# sensors.net
KiCad netlist of a schematic drawn in EAGLE
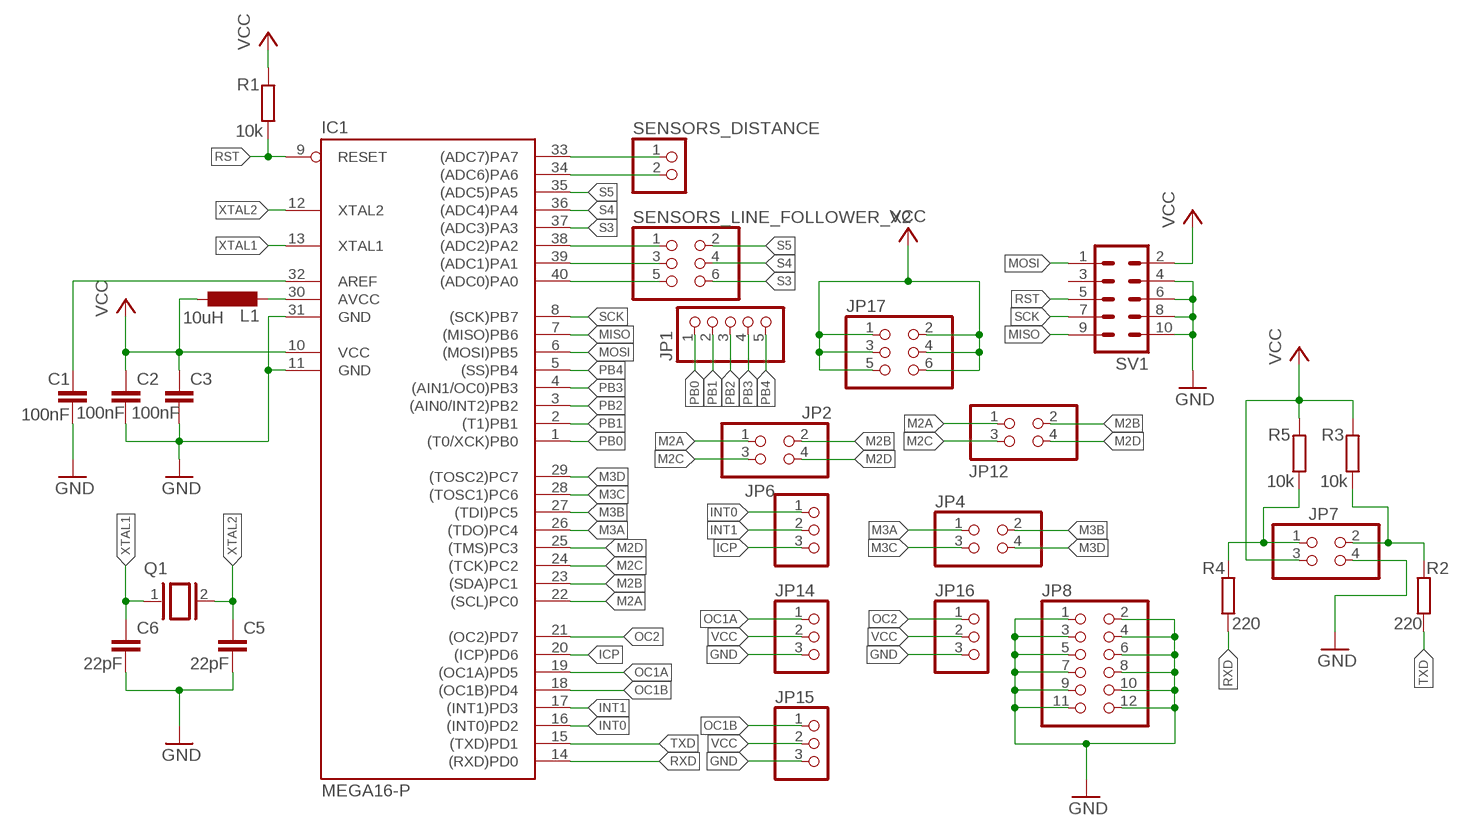
[diagram p0: schematic, sheet 1]

(export (version "E")
  (design (tool "Eeschema 10.0.6"))
  (components
    (comp (ref "C1")
      (value "100nF")
      (footprint "eagle-import:C0805")
      (libsource (lib "eagle-import") (part "C-EUC0805"))
    )
    (comp (ref "C2")
      (value "100nF")
      (footprint "eagle-import:C0805")
      (libsource (lib "eagle-import") (part "C-EUC0805"))
    )
    (comp (ref "C3")
      (value "100nF")
      (footprint "eagle-import:C0805")
      (libsource (lib "eagle-import") (part "C-EUC0805"))
    )
    (comp (ref "C5")
      (value "22pF")
      (footprint "eagle-import:C0805")
      (libsource (lib "eagle-import") (part "C-EUC0805"))
    )
    (comp (ref "C6")
      (value "22pF")
      (footprint "eagle-import:C0805")
      (libsource (lib "eagle-import") (part "C-EUC0805"))
    )
    (comp (ref "IC1")
      (value "MEGA16-P")
      (footprint "eagle-import:DIL40")
      (fields (field (name "MPN") "ATMEGA16-16PU"))
      (libsource (lib "eagle-import") (part "MEGA16-P"))
    )
    (comp (ref "JP1")
      (value "PINHD-1X5")
      (footprint "eagle-import:1X05")
      (libsource (lib "eagle-import") (part "PINHD-1X5"))
    )
    (comp (ref "JP2")
      (value "PINHD-2X2")
      (footprint "eagle-import:2X02")
      (libsource (lib "eagle-import") (part "PINHD-2X2"))
    )
    (comp (ref "JP4")
      (value "PINHD-2X2")
      (footprint "eagle-import:2X02")
      (libsource (lib "eagle-import") (part "PINHD-2X2"))
    )
    (comp (ref "JP6")
      (value "PINHD-1X3")
      (footprint "eagle-import:1X03")
      (libsource (lib "eagle-import") (part "PINHD-1X3"))
    )
    (comp (ref "JP7")
      (value "PINHD-2X2")
      (footprint "eagle-import:2X02")
      (libsource (lib "eagle-import") (part "PINHD-2X2"))
    )
    (comp (ref "JP8")
      (value "PINHD-2X6")
      (footprint "eagle-import:2X06")
      (libsource (lib "eagle-import") (part "PINHD-2X6"))
    )
    (comp (ref "JP12")
      (value "PINHD-2X2")
      (footprint "eagle-import:2X02")
      (libsource (lib "eagle-import") (part "PINHD-2X2"))
    )
    (comp (ref "JP14")
      (value "PINHD-1X3")
      (footprint "eagle-import:1X03")
      (libsource (lib "eagle-import") (part "PINHD-1X3"))
    )
    (comp (ref "JP15")
      (value "PINHD-1X3")
      (footprint "eagle-import:1X03")
      (libsource (lib "eagle-import") (part "PINHD-1X3"))
    )
    (comp (ref "JP16")
      (value "PINHD-1X3")
      (footprint "eagle-import:1X03")
      (libsource (lib "eagle-import") (part "PINHD-1X3"))
    )
    (comp (ref "JP17")
      (value "PINHD-2X3")
      (footprint "eagle-import:2X03")
      (libsource (lib "eagle-import") (part "PINHD-2X3"))
    )
    (comp (ref "L1")
      (value "10uH")
      (footprint "eagle-import:0207_7")
      (libsource (lib "eagle-import") (part "L-EU0207/7"))
    )
    (comp (ref "Q1")
      (value "XTAL/S")
      (footprint "eagle-import:QS")
      (libsource (lib "eagle-import") (part "XTAL/S"))
    )
    (comp (ref "R1")
      (value "10k")
      (footprint "eagle-import:R0805")
      (libsource (lib "eagle-import") (part "R-EU_R0805"))
    )
    (comp (ref "R2")
      (value "220")
      (footprint "eagle-import:R0805")
      (libsource (lib "eagle-import") (part "R-EU_R0805"))
    )
    (comp (ref "R3")
      (value "10k")
      (footprint "eagle-import:R0805")
      (libsource (lib "eagle-import") (part "R-EU_R0805"))
    )
    (comp (ref "R4")
      (value "220")
      (footprint "eagle-import:R0805")
      (libsource (lib "eagle-import") (part "R-EU_R0805"))
    )
    (comp (ref "R5")
      (value "10k")
      (footprint "eagle-import:R0805")
      (libsource (lib "eagle-import") (part "R-EU_R0805"))
    )
    (comp (ref "SENSORS_DISTANCE")
      (value "PINHD-1X2")
      (footprint "eagle-import:1X02")
      (libsource (lib "eagle-import") (part "PINHD-1X2"))
    )
    (comp (ref "SENSORS_LINE_FOLLOWER_X2")
      (value "PINHD-2X3")
      (footprint "eagle-import:2X03")
      (libsource (lib "eagle-import") (part "PINHD-2X3"))
    )
    (comp (ref "SV1")
      (value "ML10")
      (footprint "eagle-import:ML10")
      (libsource (lib "eagle-import") (part "ML10"))
    )
  )
  (nets
    (net (code "1") (name "GND") (class "Default")
      (node (ref "C1") (pin "2") (pinfunction "2_2") (pintype "passive"))
      (node (ref "C2") (pin "2") (pinfunction "2_2") (pintype "passive"))
      (node (ref "C3") (pin "2") (pinfunction "2_2") (pintype "passive"))
      (node (ref "C5") (pin "2") (pinfunction "2_2") (pintype "passive"))
      (node (ref "C6") (pin "2") (pinfunction "2_2") (pintype "passive"))
      (node (ref "IC1") (pin "11") (pinfunction "GND_11") (pintype "power_in"))
      (node (ref "IC1") (pin "31") (pinfunction "GND_31") (pintype "power_in"))
      (node (ref "JP14") (pin "3") (pinfunction "3_3") (pintype "passive"))
      (node (ref "JP15") (pin "3") (pinfunction "3_3") (pintype "passive"))
      (node (ref "JP16") (pin "3") (pinfunction "3_3") (pintype "passive"))
      (node (ref "JP7") (pin "4") (pinfunction "4_4") (pintype "passive"))
      (node (ref "JP8") (pin "1") (pinfunction "1_1") (pintype "passive"))
      (node (ref "JP8") (pin "10") (pinfunction "10_10") (pintype "passive"))
      (node (ref "JP8") (pin "11") (pinfunction "11_11") (pintype "passive"))
      (node (ref "JP8") (pin "12") (pinfunction "12_12") (pintype "passive"))
      (node (ref "JP8") (pin "2") (pinfunction "2_2") (pintype "passive"))
      (node (ref "JP8") (pin "3") (pinfunction "3_3") (pintype "passive"))
      (node (ref "JP8") (pin "4") (pinfunction "4_4") (pintype "passive"))
      (node (ref "JP8") (pin "5") (pinfunction "5_5") (pintype "passive"))
      (node (ref "JP8") (pin "6") (pinfunction "6_6") (pintype "passive"))
      (node (ref "JP8") (pin "7") (pinfunction "7_7") (pintype "passive"))
      (node (ref "JP8") (pin "8") (pinfunction "8_8") (pintype "passive"))
      (node (ref "JP8") (pin "9") (pinfunction "9_9") (pintype "passive"))
      (node (ref "SV1") (pin "10") (pinfunction "10_10") (pintype "passive"))
      (node (ref "SV1") (pin "4") (pinfunction "4_4") (pintype "passive"))
      (node (ref "SV1") (pin "6") (pinfunction "6_6") (pintype "passive"))
      (node (ref "SV1") (pin "8") (pinfunction "8_8") (pintype "passive"))
    )
    (net (code "2") (name "ICP") (class "Default")
      (node (ref "IC1") (pin "20") (pinfunction "(ICP)PD6_20") (pintype "bidirectional"))
      (node (ref "JP6") (pin "3") (pinfunction "3_3") (pintype "passive"))
    )
    (net (code "3") (name "INT0") (class "Default")
      (node (ref "IC1") (pin "16") (pinfunction "(INT0)PD2_16") (pintype "bidirectional"))
      (node (ref "JP6") (pin "1") (pinfunction "1_1") (pintype "passive"))
    )
    (net (code "4") (name "INT1") (class "Default")
      (node (ref "IC1") (pin "17") (pinfunction "(INT1)PD3_17") (pintype "bidirectional"))
      (node (ref "JP6") (pin "2") (pinfunction "2_2") (pintype "passive"))
    )
    (net (code "5") (name "M2A") (class "Default")
      (node (ref "IC1") (pin "22") (pinfunction "(SCL)PC0_22") (pintype "bidirectional"))
      (node (ref "JP12") (pin "1") (pinfunction "1_1") (pintype "passive"))
      (node (ref "JP2") (pin "1") (pinfunction "1_1") (pintype "passive"))
    )
    (net (code "6") (name "M2B") (class "Default")
      (node (ref "IC1") (pin "23") (pinfunction "(SDA)PC1_23") (pintype "bidirectional"))
      (node (ref "JP12") (pin "2") (pinfunction "2_2") (pintype "passive"))
      (node (ref "JP2") (pin "2") (pinfunction "2_2") (pintype "passive"))
    )
    (net (code "7") (name "M2C") (class "Default")
      (node (ref "IC1") (pin "24") (pinfunction "(TCK)PC2_24") (pintype "bidirectional"))
      (node (ref "JP12") (pin "3") (pinfunction "3_3") (pintype "passive"))
      (node (ref "JP2") (pin "3") (pinfunction "3_3") (pintype "passive"))
    )
    (net (code "8") (name "M2D") (class "Default")
      (node (ref "IC1") (pin "25") (pinfunction "(TMS)PC3_25") (pintype "bidirectional"))
      (node (ref "JP12") (pin "4") (pinfunction "4_4") (pintype "passive"))
      (node (ref "JP2") (pin "4") (pinfunction "4_4") (pintype "passive"))
    )
    (net (code "9") (name "M3A") (class "Default")
      (node (ref "IC1") (pin "26") (pinfunction "(TDO)PC4_26") (pintype "bidirectional"))
      (node (ref "JP4") (pin "1") (pinfunction "1_1") (pintype "passive"))
    )
    (net (code "10") (name "M3B") (class "Default")
      (node (ref "IC1") (pin "27") (pinfunction "(TDI)PC5_27") (pintype "bidirectional"))
      (node (ref "JP4") (pin "2") (pinfunction "2_2") (pintype "passive"))
    )
    (net (code "11") (name "M3C") (class "Default")
      (node (ref "IC1") (pin "28") (pinfunction "(TOSC1)PC6_28") (pintype "bidirectional"))
      (node (ref "JP4") (pin "3") (pinfunction "3_3") (pintype "passive"))
    )
    (net (code "12") (name "M3D") (class "Default")
      (node (ref "IC1") (pin "29") (pinfunction "(TOSC2)PC7_29") (pintype "bidirectional"))
      (node (ref "JP4") (pin "4") (pinfunction "4_4") (pintype "passive"))
    )
    (net (code "13") (name "MISO") (class "Default")
      (node (ref "IC1") (pin "7") (pinfunction "(MISO)PB6_7") (pintype "bidirectional"))
      (node (ref "SV1") (pin "9") (pinfunction "9_9") (pintype "passive"))
    )
    (net (code "14") (name "MOSI") (class "Default")
      (node (ref "IC1") (pin "6") (pinfunction "(MOSI)PB5_6") (pintype "bidirectional"))
      (node (ref "SV1") (pin "1") (pinfunction "1_1") (pintype "passive"))
    )
    (net (code "15") (name "Net-(IC1-(ADC0)PA0)") (class "Default")
      (node (ref "IC1") (pin "40") (pinfunction "(ADC0)PA0_40") (pintype "bidirectional"))
      (node (ref "SENSORS_LINE_FOLLOWER_X2") (pin "5") (pinfunction "5_5") (pintype "passive"))
    )
    (net (code "16") (name "Net-(IC1-(ADC1)PA1)") (class "Default")
      (node (ref "IC1") (pin "39") (pinfunction "(ADC1)PA1_39") (pintype "bidirectional"))
      (node (ref "SENSORS_LINE_FOLLOWER_X2") (pin "3") (pinfunction "3_3") (pintype "passive"))
    )
    (net (code "17") (name "Net-(IC1-(ADC2)PA2)") (class "Default")
      (node (ref "IC1") (pin "38") (pinfunction "(ADC2)PA2_38") (pintype "bidirectional"))
      (node (ref "SENSORS_LINE_FOLLOWER_X2") (pin "1") (pinfunction "1_1") (pintype "passive"))
    )
    (net (code "18") (name "Net-(IC1-(ADC6)PA6)") (class "Default")
      (node (ref "IC1") (pin "34") (pinfunction "(ADC6)PA6_34") (pintype "bidirectional"))
      (node (ref "SENSORS_DISTANCE") (pin "2") (pinfunction "2_2") (pintype "passive"))
    )
    (net (code "19") (name "Net-(IC1-(ADC7)PA7)") (class "Default")
      (node (ref "IC1") (pin "33") (pinfunction "(ADC7)PA7_33") (pintype "bidirectional"))
      (node (ref "SENSORS_DISTANCE") (pin "1") (pinfunction "1_1") (pintype "passive"))
    )
    (net (code "20") (name "Net-(IC1-AREF)") (class "Default")
      (node (ref "C1") (pin "1") (pinfunction "1_1") (pintype "passive"))
      (node (ref "IC1") (pin "32") (pinfunction "AREF_32") (pintype "passive"))
    )
    (net (code "21") (name "Net-(IC1-AVCC)") (class "Default")
      (node (ref "IC1") (pin "30") (pinfunction "AVCC_30") (pintype "power_in"))
      (node (ref "L1") (pin "2") (pinfunction "2_2") (pintype "passive"))
    )
    (net (code "22") (name "Net-(JP7-Pad1)") (class "Default")
      (node (ref "JP7") (pin "1") (pinfunction "1_1") (pintype "passive"))
      (node (ref "R4") (pin "2") (pinfunction "2_2") (pintype "passive"))
      (node (ref "R5") (pin "1") (pinfunction "1_1") (pintype "passive"))
    )
    (net (code "23") (name "Net-(JP7-Pad2)") (class "Default")
      (node (ref "JP7") (pin "2") (pinfunction "2_2") (pintype "passive"))
      (node (ref "R2") (pin "2") (pinfunction "2_2") (pintype "passive"))
      (node (ref "R3") (pin "1") (pinfunction "1_1") (pintype "passive"))
    )
    (net (code "24") (name "OC1A") (class "Default")
      (node (ref "IC1") (pin "19") (pinfunction "(OC1A)PD5_19") (pintype "bidirectional"))
      (node (ref "JP14") (pin "1") (pinfunction "1_1") (pintype "passive"))
    )
    (net (code "25") (name "OC1B") (class "Default")
      (node (ref "IC1") (pin "18") (pinfunction "(OC1B)PD4_18") (pintype "bidirectional"))
      (node (ref "JP15") (pin "1") (pinfunction "1_1") (pintype "passive"))
    )
    (net (code "26") (name "OC2") (class "Default")
      (node (ref "IC1") (pin "21") (pinfunction "(OC2)PD7_21") (pintype "bidirectional"))
      (node (ref "JP16") (pin "1") (pinfunction "1_1") (pintype "passive"))
    )
    (net (code "27") (name "PB0") (class "Default")
      (node (ref "IC1") (pin "1") (pinfunction "(T0/XCK)PB0_1") (pintype "bidirectional"))
      (node (ref "JP1") (pin "1") (pinfunction "1_1") (pintype "passive"))
    )
    (net (code "28") (name "PB1") (class "Default")
      (node (ref "IC1") (pin "2") (pinfunction "(T1)PB1_2") (pintype "bidirectional"))
      (node (ref "JP1") (pin "2") (pinfunction "2_2") (pintype "passive"))
    )
    (net (code "29") (name "PB2") (class "Default")
      (node (ref "IC1") (pin "3") (pinfunction "(AIN0/INT2)PB2_3") (pintype "bidirectional"))
      (node (ref "JP1") (pin "3") (pinfunction "3_3") (pintype "passive"))
    )
    (net (code "30") (name "PB3") (class "Default")
      (node (ref "IC1") (pin "4") (pinfunction "(AIN1/OC0)PB3_4") (pintype "bidirectional"))
      (node (ref "JP1") (pin "4") (pinfunction "4_4") (pintype "passive"))
    )
    (net (code "31") (name "PB4") (class "Default")
      (node (ref "IC1") (pin "5") (pinfunction "(SS)PB4_5") (pintype "bidirectional"))
      (node (ref "JP1") (pin "5") (pinfunction "5_5") (pintype "passive"))
    )
    (net (code "32") (name "RST") (class "Default")
      (node (ref "IC1") (pin "9") (pinfunction "RESET_9") (pintype "input"))
      (node (ref "R1") (pin "1") (pinfunction "1_1") (pintype "passive"))
      (node (ref "SV1") (pin "5") (pinfunction "5_5") (pintype "passive"))
    )
    (net (code "33") (name "RXD") (class "Default")
      (node (ref "IC1") (pin "14") (pinfunction "(RXD)PD0_14") (pintype "bidirectional"))
      (node (ref "R4") (pin "1") (pinfunction "1_1") (pintype "passive"))
    )
    (net (code "34") (name "S3") (class "Default")
      (node (ref "IC1") (pin "37") (pinfunction "(ADC3)PA3_37") (pintype "bidirectional"))
      (node (ref "SENSORS_LINE_FOLLOWER_X2") (pin "6") (pinfunction "6_6") (pintype "passive"))
    )
    (net (code "35") (name "S4") (class "Default")
      (node (ref "IC1") (pin "36") (pinfunction "(ADC4)PA4_36") (pintype "bidirectional"))
      (node (ref "SENSORS_LINE_FOLLOWER_X2") (pin "4") (pinfunction "4_4") (pintype "passive"))
    )
    (net (code "36") (name "S5") (class "Default")
      (node (ref "IC1") (pin "35") (pinfunction "(ADC5)PA5_35") (pintype "bidirectional"))
      (node (ref "SENSORS_LINE_FOLLOWER_X2") (pin "2") (pinfunction "2_2") (pintype "passive"))
    )
    (net (code "37") (name "SCK") (class "Default")
      (node (ref "IC1") (pin "8") (pinfunction "(SCK)PB7_8") (pintype "bidirectional"))
      (node (ref "SV1") (pin "7") (pinfunction "7_7") (pintype "passive"))
    )
    (net (code "38") (name "TXD") (class "Default")
      (node (ref "IC1") (pin "15") (pinfunction "(TXD)PD1_15") (pintype "bidirectional"))
      (node (ref "R2") (pin "1") (pinfunction "1_1") (pintype "passive"))
    )
    (net (code "39") (name "VCC") (class "Default")
      (node (ref "C2") (pin "1") (pinfunction "1_1") (pintype "passive"))
      (node (ref "C3") (pin "1") (pinfunction "1_1") (pintype "passive"))
      (node (ref "IC1") (pin "10") (pinfunction "VCC_10") (pintype "power_in"))
      (node (ref "JP14") (pin "2") (pinfunction "2_2") (pintype "passive"))
      (node (ref "JP15") (pin "2") (pinfunction "2_2") (pintype "passive"))
      (node (ref "JP16") (pin "2") (pinfunction "2_2") (pintype "passive"))
      (node (ref "JP17") (pin "1") (pinfunction "1_1") (pintype "passive"))
      (node (ref "JP17") (pin "2") (pinfunction "2_2") (pintype "passive"))
      (node (ref "JP17") (pin "3") (pinfunction "3_3") (pintype "passive"))
      (node (ref "JP17") (pin "4") (pinfunction "4_4") (pintype "passive"))
      (node (ref "JP17") (pin "5") (pinfunction "5_5") (pintype "passive"))
      (node (ref "JP17") (pin "6") (pinfunction "6_6") (pintype "passive"))
      (node (ref "JP7") (pin "3") (pinfunction "3_3") (pintype "passive"))
      (node (ref "L1") (pin "1") (pinfunction "1_1") (pintype "passive"))
      (node (ref "R1") (pin "2") (pinfunction "2_2") (pintype "passive"))
      (node (ref "R3") (pin "2") (pinfunction "2_2") (pintype "passive"))
      (node (ref "R5") (pin "2") (pinfunction "2_2") (pintype "passive"))
      (node (ref "SV1") (pin "2") (pinfunction "2_2") (pintype "passive"))
    )
    (net (code "40") (name "XTAL1") (class "Default")
      (node (ref "C6") (pin "1") (pinfunction "1_1") (pintype "passive"))
      (node (ref "IC1") (pin "13") (pinfunction "XTAL1_13") (pintype "bidirectional"))
      (node (ref "Q1") (pin "1") (pinfunction "1_1") (pintype "passive"))
    )
    (net (code "41") (name "XTAL2") (class "Default")
      (node (ref "C5") (pin "1") (pinfunction "1_1") (pintype "passive"))
      (node (ref "IC1") (pin "12") (pinfunction "XTAL2_12") (pintype "bidirectional"))
      (node (ref "Q1") (pin "2") (pinfunction "2_2") (pintype "passive"))
    )
    (net (code "42") (name "unconnected-(SV1-Pad3)") (class "Default")
      (node (ref "SV1") (pin "3") (pinfunction "3_3") (pintype "passive"))
    )
  )
)
